# VI_monitor.net
KiCad netlist of a schematic drawn in Altium Designer
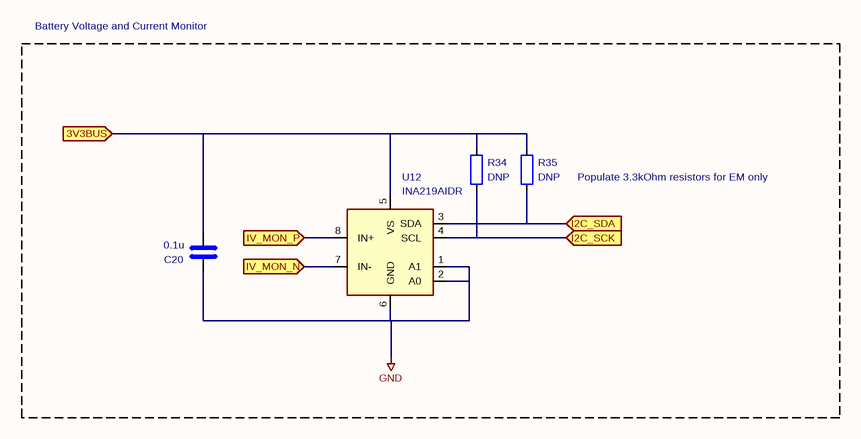
[diagram p0: VI_monitor.SchDoc]

(export (version "E")
  (design (tool "Eeschema 10.0.6"))
  (components
    (comp (ref "C20") (value "0.1u") (libsource (lib "Device") (part "C")))
    (comp (ref "R34") (value "DNP") (libsource (lib "Device") (part "R")))
    (comp (ref "R35") (value "DNP") (libsource (lib "Device") (part "R")))
    (comp (ref "U12") (value "INA219AIDR") (libsource (lib "Analog_ADC") (part "INA219AxD")))
  )
  (nets
    (net (code "1") (name "/3V3BUS") (class "Default")
      (node (ref "C20") (pin "2") (pinfunction "2_2") (pintype "passive"))
      (node (ref "R34") (pin "2") (pinfunction "2_2") (pintype "passive"))
      (node (ref "R35") (pin "2") (pinfunction "2_2") (pintype "passive"))
      (node (ref "U12") (pin "5") (pinfunction "VS_5") (pintype "passive"))
    )
    (net (code "2") (name "/I2C_SCK") (class "Default")
      (node (ref "R34") (pin "1") (pinfunction "1_1") (pintype "passive"))
      (node (ref "U12") (pin "4") (pinfunction "SCL_4") (pintype "passive"))
    )
    (net (code "3") (name "/I2C_SDA") (class "Default")
      (node (ref "R35") (pin "1") (pinfunction "1_1") (pintype "passive"))
      (node (ref "U12") (pin "3") (pinfunction "SDA_3") (pintype "passive"))
    )
    (net (code "4") (name "/IV_MON_N") (class "Default")
      (node (ref "U12") (pin "7") (pinfunction "IN-_7") (pintype "passive"))
    )
    (net (code "5") (name "/IV_MON_P") (class "Default")
      (node (ref "U12") (pin "8") (pinfunction "IN+_8") (pintype "passive"))
    )
    (net (code "6") (name "GND") (class "Default")
      (node (ref "C20") (pin "1") (pinfunction "1_1") (pintype "passive"))
      (node (ref "U12") (pin "1") (pinfunction "A1_1") (pintype "passive"))
      (node (ref "U12") (pin "2") (pinfunction "A0_2") (pintype "passive"))
      (node (ref "U12") (pin "6") (pinfunction "GND_6") (pintype "passive"))
    )
  )
)
